# IO_Expandor.net
KiCad netlist of a schematic drawn in Altium Designer
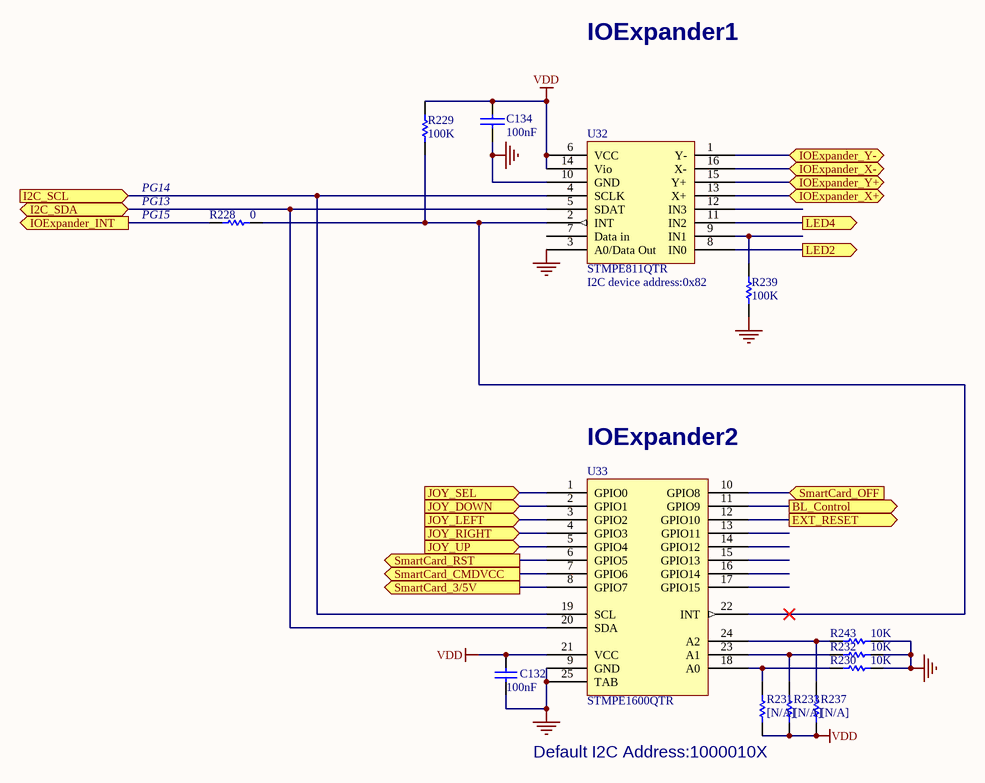
[diagram p0: IO_Expandor.SchDoc]

(export (version "E")
  (design (tool "Eeschema 10.0.6"))
  (components
    (comp (ref "C132")
      (value "100nF")
      (footprint "0402C")
      (description "Capacitor")
      (fields (field (name "PUBLISHER") "Altium Limited"))
      (libsource (lib "Miscellaneous Devices") (part "Cap"))
    )
    (comp (ref "C134")
      (value "100nF")
      (footprint "0402C")
      (description "Capacitor")
      (libsource (lib "*") (part "CAP"))
    )
    (comp (ref "R228")
      (value "0")
      (footprint "0603R")
      (description "Resistor")
      (fields (field (name "PUBLISHER") "Altium Limited"))
      (libsource (lib "Miscellaneous Devices") (part "Res1"))
    )
    (comp (ref "R229")
      (value "100K")
      (footprint "0402R")
      (description "Resistor")
      (fields (field (name "PUBLISHER") "Altium Limited"))
      (libsource (lib "Miscellaneous Devices") (part "Res1"))
    )
    (comp (ref "R230")
      (value "10K")
      (footprint "0402R")
      (description "Resistor")
      (fields (field (name "PUBLISHER") "Altium Limited"))
      (libsource (lib "Miscellaneous Devices") (part "res1"))
    )
    (comp (ref "R231")
      (value "[N/A]")
      (footprint "0603R")
      (description "Resistor")
      (fields (field (name "PUBLISHER") "Altium Limited"))
      (libsource (lib "Miscellaneous Devices") (part "Res1"))
    )
    (comp (ref "R232")
      (value "10K")
      (footprint "0402R")
      (description "Resistor")
      (fields (field (name "PUBLISHER") "Altium Limited"))
      (libsource (lib "Miscellaneous Devices") (part "res1"))
    )
    (comp (ref "R233")
      (value "[N/A]")
      (footprint "0603R")
      (description "Resistor")
      (fields (field (name "PUBLISHER") "Altium Limited"))
      (libsource (lib "Miscellaneous Devices") (part "Res1"))
    )
    (comp (ref "R237")
      (value "[N/A]")
      (footprint "0603R")
      (description "Resistor")
      (fields (field (name "PUBLISHER") "Altium Limited"))
      (libsource (lib "Miscellaneous Devices") (part "Res1"))
    )
    (comp (ref "R239")
      (value "100K")
      (footprint "0402R")
      (description "Resistor")
      (fields (field (name "PUBLISHER") "Altium Limited"))
      (libsource (lib "Miscellaneous Devices") (part "Res1"))
    )
    (comp (ref "R243")
      (value "10K")
      (footprint "0402R")
      (description "Resistor")
      (fields (field (name "PUBLISHER") "Altium Limited"))
      (libsource (lib "Miscellaneous Devices") (part "res1"))
    )
    (comp (ref "U32")
      (value "STMPE811QTR")
      (footprint "QFN16_0R5_3X3")
      (libsource (lib "MB784") (part "STMPE811"))
    )
    (comp (ref "U33")
      (value "STMPE1600QTR")
      (footprint "QFN24_0R5_4X4")
      (libsource (lib "mb1045") (part "STMPE1600"))
    )
  )
  (nets
    (net (code "1") (name "/BL_Control") (class "Default")
      (node (ref "U33") (pin "11") (pinfunction "GPIO9_11") (pintype "passive"))
    )
    (net (code "2") (name "/EXT_RESET") (class "Default")
      (node (ref "U33") (pin "12") (pinfunction "GPIO10_12") (pintype "passive"))
    )
    (net (code "3") (name "/I2C_SCL") (class "Default")
      (node (ref "U32") (pin "4") (pinfunction "SCLK_4") (pintype "passive"))
      (node (ref "U33") (pin "19") (pinfunction "SCL_19") (pintype "passive"))
    )
    (net (code "4") (name "/I2C_SDA") (class "Default")
      (node (ref "U32") (pin "5") (pinfunction "SDAT_5") (pintype "passive"))
      (node (ref "U33") (pin "20") (pinfunction "SDA_20") (pintype "passive"))
    )
    (net (code "5") (name "/IOExpander_INT") (class "Default")
      (node (ref "R228") (pin "1") (pinfunction "1_1") (pintype "passive"))
    )
    (net (code "6") (name "/IOExpander_X+") (class "Default")
      (node (ref "U32") (pin "13") (pinfunction "X+_13") (pintype "passive"))
    )
    (net (code "7") (name "/IOExpander_X-") (class "Default")
      (node (ref "U32") (pin "16") (pinfunction "X-_16") (pintype "passive"))
    )
    (net (code "8") (name "/IOExpander_Y+") (class "Default")
      (node (ref "U32") (pin "15") (pinfunction "Y+_15") (pintype "passive"))
    )
    (net (code "9") (name "/IOExpander_Y-") (class "Default")
      (node (ref "U32") (pin "1") (pinfunction "Y-_1") (pintype "passive"))
    )
    (net (code "10") (name "/JOY_DOWN") (class "Default")
      (node (ref "U33") (pin "2") (pinfunction "GPIO1_2") (pintype "passive"))
    )
    (net (code "11") (name "/JOY_LEFT") (class "Default")
      (node (ref "U33") (pin "3") (pinfunction "GPIO2_3") (pintype "passive"))
    )
    (net (code "12") (name "/JOY_RIGHT") (class "Default")
      (node (ref "U33") (pin "4") (pinfunction "GPIO3_4") (pintype "passive"))
    )
    (net (code "13") (name "/JOY_SEL") (class "Default")
      (node (ref "U33") (pin "1") (pinfunction "GPIO0_1") (pintype "passive"))
    )
    (net (code "14") (name "/JOY_UP") (class "Default")
      (node (ref "U33") (pin "5") (pinfunction "GPIO4_5") (pintype "passive"))
    )
    (net (code "15") (name "/LED2") (class "Default")
      (node (ref "U32") (pin "8") (pinfunction "IN0_8") (pintype "passive"))
    )
    (net (code "16") (name "/LED4") (class "Default")
      (node (ref "U32") (pin "11") (pinfunction "IN2_11") (pintype "passive"))
    )
    (net (code "17") (name "/SmartCard_3{slash}5V") (class "Default")
      (node (ref "U33") (pin "8") (pinfunction "GPIO7_8") (pintype "passive"))
    )
    (net (code "18") (name "/SmartCard_CMDVCC") (class "Default")
      (node (ref "U33") (pin "7") (pinfunction "GPIO6_7") (pintype "passive"))
    )
    (net (code "19") (name "/SmartCard_OFF") (class "Default")
      (node (ref "U33") (pin "10") (pinfunction "GPIO8_10") (pintype "passive"))
    )
    (net (code "20") (name "/SmartCard_RST") (class "Default")
      (node (ref "U33") (pin "6") (pinfunction "GPIO5_6") (pintype "passive"))
    )
    (net (code "21") (name "GND") (class "Default")
      (node (ref "C132") (pin "2") (pinfunction "2_2") (pintype "passive"))
      (node (ref "C134") (pin "2") (pinfunction "2_2") (pintype "passive"))
      (node (ref "R230") (pin "1") (pinfunction "1_1") (pintype "passive"))
      (node (ref "R232") (pin "1") (pinfunction "1_1") (pintype "passive"))
      (node (ref "R239") (pin "2") (pinfunction "2_2") (pintype "passive"))
      (node (ref "R243") (pin "1") (pinfunction "1_1") (pintype "passive"))
      (node (ref "U32") (pin "10") (pinfunction "GND_10") (pintype "passive"))
      (node (ref "U32") (pin "3") (pinfunction "A0/Data_Out_3") (pintype "passive"))
      (node (ref "U33") (pin "25") (pinfunction "TAB_25") (pintype "passive"))
      (node (ref "U33") (pin "9") (pinfunction "GND_9") (pintype "passive"))
    )
    (net (code "22") (name "Net-(U32-IN1)") (class "Default")
      (node (ref "R239") (pin "1") (pinfunction "1_1") (pintype "passive"))
      (node (ref "U32") (pin "9") (pinfunction "IN1_9") (pintype "passive"))
    )
    (net (code "23") (name "Net-(U32-INT)") (class "Default")
      (node (ref "R228") (pin "2") (pinfunction "2_2") (pintype "passive"))
      (node (ref "R229") (pin "2") (pinfunction "2_2") (pintype "passive"))
      (node (ref "U32") (pin "2") (pinfunction "INT_2") (pintype "output"))
      (node (ref "U33") (pin "22") (pinfunction "INT_22") (pintype "output"))
    )
    (net (code "24") (name "Net-(U33-A0)") (class "Default")
      (node (ref "R230") (pin "2") (pinfunction "2_2") (pintype "passive"))
      (node (ref "R231") (pin "2") (pinfunction "2_2") (pintype "passive"))
      (node (ref "U33") (pin "18") (pinfunction "A0_18") (pintype "passive"))
    )
    (net (code "25") (name "Net-(U33-A1)") (class "Default")
      (node (ref "R232") (pin "2") (pinfunction "2_2") (pintype "passive"))
      (node (ref "R233") (pin "2") (pinfunction "2_2") (pintype "passive"))
      (node (ref "U33") (pin "23") (pinfunction "A1_23") (pintype "passive"))
    )
    (net (code "26") (name "Net-(U33-A2)") (class "Default")
      (node (ref "R237") (pin "2") (pinfunction "2_2") (pintype "passive"))
      (node (ref "R243") (pin "2") (pinfunction "2_2") (pintype "passive"))
      (node (ref "U33") (pin "24") (pinfunction "A2_24") (pintype "passive"))
    )
    (net (code "27") (name "VDD") (class "Default")
      (node (ref "C132") (pin "1") (pinfunction "1_1") (pintype "passive"))
      (node (ref "C134") (pin "1") (pinfunction "1_1") (pintype "passive"))
      (node (ref "R229") (pin "1") (pinfunction "1_1") (pintype "passive"))
      (node (ref "R231") (pin "1") (pinfunction "1_1") (pintype "passive"))
      (node (ref "R233") (pin "1") (pinfunction "1_1") (pintype "passive"))
      (node (ref "R237") (pin "1") (pinfunction "1_1") (pintype "passive"))
      (node (ref "U32") (pin "14") (pinfunction "Vio_14") (pintype "passive"))
      (node (ref "U32") (pin "6") (pinfunction "VCC_6") (pintype "passive"))
      (node (ref "U33") (pin "21") (pinfunction "VCC_21") (pintype "passive"))
    )
    (net (code "28") (name "unconnected-(U32-Data_in-Pad7)") (class "Default")
      (node (ref "U32") (pin "7") (pinfunction "Data_in_7") (pintype "passive"))
    )
    (net (code "29") (name "unconnected-(U32-IN3-Pad12)") (class "Default")
      (node (ref "U32") (pin "12") (pinfunction "IN3_12") (pintype "passive"))
    )
    (net (code "30") (name "unconnected-(U33-GPIO11-Pad13)") (class "Default")
      (node (ref "U33") (pin "13") (pinfunction "GPIO11_13") (pintype "passive"))
    )
    (net (code "31") (name "unconnected-(U33-GPIO12-Pad14)") (class "Default")
      (node (ref "U33") (pin "14") (pinfunction "GPIO12_14") (pintype "passive"))
    )
    (net (code "32") (name "unconnected-(U33-GPIO13-Pad15)") (class "Default")
      (node (ref "U33") (pin "15") (pinfunction "GPIO13_15") (pintype "passive"))
    )
    (net (code "33") (name "unconnected-(U33-GPIO14-Pad16)") (class "Default")
      (node (ref "U33") (pin "16") (pinfunction "GPIO14_16") (pintype "passive"))
    )
    (net (code "34") (name "unconnected-(U33-GPIO15-Pad17)") (class "Default")
      (node (ref "U33") (pin "17") (pinfunction "GPIO15_17") (pintype "passive"))
    )
  )
)
